# ZHSD-USB-UART.net
KiCad netlist of a schematic drawn in Altium Designer
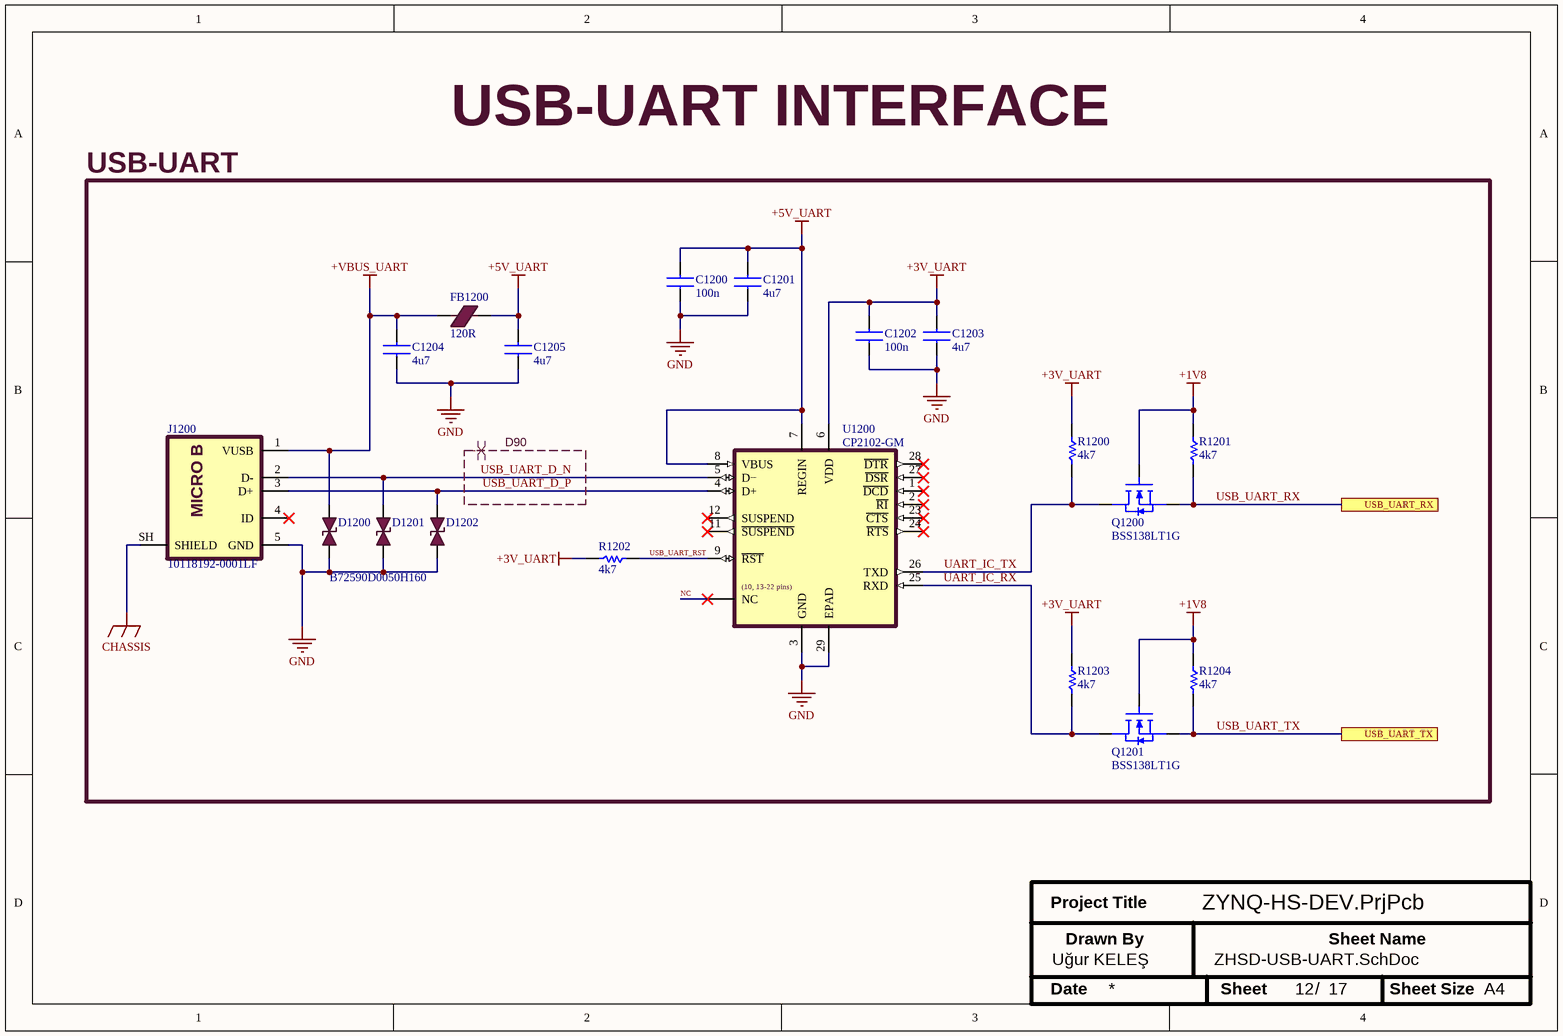
[diagram p0: ZHSD-USB-UART.SchDoc]

(export (version "E")
  (design (tool "Eeschema 10.0.6"))
  (components
    (comp (ref "C1200")
      (value "100n")
      (footprint "0603CAPC1608X09N")
      (description "CAP CER 0.1UF 16V X7R 0402 (1005) ±10%")
      (fields (field (name "MANUFACTURER") "Murata Electronics") (field (name "MPN") "GRM155R71C104KA88J"))
      (libsource (lib "UK_Library") (part "GRM155R71C104KA88J"))
    )
    (comp (ref "C1201")
      (value "4u7")
      (footprint "0603CAPC1608X09N")
      (description "CAP CER 4.7UF 10V X5R 0603 (1608) ±10%")
      (fields
        (field (name "MANUFACTURER") "Samsung Electro-Mechanics")
        (field (name "MPN") "CL10A475KP8NNNC")
      )
      (libsource (lib "UK_Library") (part "CL10A475KP8NNNC"))
    )
    (comp (ref "C1202")
      (value "100n")
      (footprint "0603CAPC1608X09N")
      (description "CAP CER 0.1UF 16V X7R 0402 (1005) ±10%")
      (fields (field (name "MANUFACTURER") "Murata Electronics") (field (name "MPN") "GRM155R71C104KA88J"))
      (libsource (lib "UK_Library") (part "GRM155R71C104KA88J"))
    )
    (comp (ref "C1203")
      (value "4u7")
      (footprint "0603CAPC1608X09N")
      (description "CAP CER 4.7UF 10V X5R 0603 (1608) ±10%")
      (fields
        (field (name "MANUFACTURER") "Samsung Electro-Mechanics")
        (field (name "MPN") "CL10A475KP8NNNC")
      )
      (libsource (lib "UK_Library") (part "CL10A475KP8NNNC"))
    )
    (comp (ref "C1204")
      (value "4u7")
      (footprint "0603CAPC1608X09N")
      (description "CAP CER 4.7UF 10V X5R 0603 (1608) ±10%")
      (fields
        (field (name "MANUFACTURER") "Samsung Electro-Mechanics")
        (field (name "MPN") "CL10A475KP8NNNC")
      )
      (libsource (lib "UK_Library") (part "CL10A475KP8NNNC"))
    )
    (comp (ref "C1205")
      (value "4u7")
      (footprint "0603CAPC1608X09N")
      (description "CAP CER 4.7UF 10V X5R 0603 (1608) ±10%")
      (fields
        (field (name "MANUFACTURER") "Samsung Electro-Mechanics")
        (field (name "MPN") "CL10A475KP8NNNC")
      )
      (libsource (lib "UK_Library") (part "CL10A475KP8NNNC"))
    )
    (comp (ref "D1200")
      (value "B72590D0050H160")
      (footprint "0402DIOC1005X06N")
      (description "Varistor 1 Circuit Surface Mount, MLCV 0402 (1005 Metric)")
      (fields (field (name "MANUFACTURER") "EPCOS - TDK Electronics"))
      (libsource (lib "UK_Library") (part "B72590D0050H160"))
    )
    (comp (ref "D1201")
      (value "B72590D0050H160")
      (footprint "0402DIOC1005X06N")
      (description "Varistor 1 Circuit Surface Mount, MLCV 0402 (1005 Metric)")
      (fields (field (name "MANUFACTURER") "EPCOS - TDK Electronics"))
      (libsource (lib "UK_Library") (part "B72590D0050H160"))
    )
    (comp (ref "D1202")
      (value "B72590D0050H160")
      (footprint "0402DIOC1005X06N")
      (description "Varistor 1 Circuit Surface Mount, MLCV 0402 (1005 Metric)")
      (fields (field (name "MANUFACTURER") "EPCOS - TDK Electronics"))
      (libsource (lib "UK_Library") (part "B72590D0050H160"))
    )
    (comp (ref "FB1200")
      (value "120R")
      (footprint "0603INDC1608X08N")
      (description "FERRITE BEAD 120 OHM 0603 (1608) 3A 25mOhm")
      (fields (field (name "MANUFACTURER") "Murata Electronics") (field (name "MPN") "BLM18SG121TN1D"))
      (libsource (lib "UK_Library") (part "BLM18SG121TN1D"))
    )
    (comp (ref "J1200")
      (value "10118192-0001LF")
      (footprint "USB2.0 MICRO B SMD")
      (description "CONN RCPT USB2.0 MICRO B SMD R/A")
      (fields (field (name "MANUFACTURER") "Amphenol ICC (FCI)"))
      (libsource (lib "UK_Library") (part "USB-MICRO-B"))
    )
    (comp (ref "Q1200")
      (value "BSS138LT1G")
      (footprint "SOT95P237X89-3N")
      (description "N-Channel 50 V 200mA (Ta) 225mW (Ta) Surface Mount SOT-23-3 (TO-236)")
      (fields (field (name "MANUFACTURER") "onsemi"))
      (libsource (lib "UK_Library") (part "BSS138LT1G"))
    )
    (comp (ref "Q1201")
      (value "BSS138LT1G")
      (footprint "SOT95P237X89-3N")
      (description "N-Channel 50 V 200mA (Ta) 225mW (Ta) Surface Mount SOT-23-3 (TO-236)")
      (fields (field (name "MANUFACTURER") "onsemi"))
      (libsource (lib "UK_Library") (part "BSS138LT1G"))
    )
    (comp (ref "R1200")
      (value "4k7")
      (footprint "0402RESC1005X04N")
      (description "RES 4.7K OHM 5% 1/16W 0402 (1005)")
      (fields (field (name "MANUFACTURER") "YAGEO") (field (name "MPN") "RT0402FRE0780RL"))
      (libsource (lib "UK_Library") (part "RC0402JR-074K7L"))
    )
    (comp (ref "R1201")
      (value "4k7")
      (footprint "0402RESC1005X04N")
      (description "RES 4.7K OHM 5% 1/16W 0402 (1005)")
      (fields (field (name "MANUFACTURER") "YAGEO") (field (name "MPN") "RT0402FRE0780RL"))
      (libsource (lib "UK_Library") (part "RC0402JR-074K7L"))
    )
    (comp (ref "R1202")
      (value "4k7")
      (footprint "0402RESC1005X04N")
      (description "RES 4.7K OHM 5% 1/16W 0402 (1005)")
      (fields (field (name "MANUFACTURER") "YAGEO") (field (name "MPN") "RT0402FRE0780RL"))
      (libsource (lib "UK_Library") (part "RC0402JR-074K7L"))
    )
    (comp (ref "R1203")
      (value "4k7")
      (footprint "0402RESC1005X04N")
      (description "RES 4.7K OHM 5% 1/16W 0402 (1005)")
      (fields (field (name "MANUFACTURER") "YAGEO") (field (name "MPN") "RT0402FRE0780RL"))
      (libsource (lib "UK_Library") (part "RC0402JR-074K7L"))
    )
    (comp (ref "R1204")
      (value "4k7")
      (footprint "0402RESC1005X04N")
      (description "RES 4.7K OHM 5% 1/16W 0402 (1005)")
      (fields (field (name "MANUFACTURER") "YAGEO") (field (name "MPN") "RT0402FRE0780RL"))
      (libsource (lib "UK_Library") (part "RC0402JR-074K7L"))
    )
    (comp (ref "U1200")
      (value "CP2102-GM")
      (footprint "QFN50P500X500X100_HS-29N")
      (description "USB Bridge, USB to UART USB 2.0 UART Interface 28-QFN (5x5)")
      (fields (field (name "MANUFACTURER") "Silicon Labs"))
      (libsource (lib "UK_Library") (part "CP2102-GM"))
    )
  )
  (nets
    (net (code "1") (name "+1V8") (class "Default")
      (node (ref "Q1200") (pin "1") (pinfunction "G_1") (pintype "passive"))
      (node (ref "Q1201") (pin "1") (pinfunction "G_1") (pintype "passive"))
      (node (ref "R1201") (pin "1") (pinfunction "1_1") (pintype "passive"))
      (node (ref "R1204") (pin "1") (pinfunction "1_1") (pintype "passive"))
    )
    (net (code "2") (name "+3V_UART") (class "Default")
      (node (ref "C1202") (pin "2") (pinfunction "2_2") (pintype "passive"))
      (node (ref "C1203") (pin "2") (pinfunction "2_2") (pintype "passive"))
      (node (ref "R1200") (pin "1") (pinfunction "1_1") (pintype "passive"))
      (node (ref "R1202") (pin "2") (pinfunction "2_2") (pintype "passive"))
      (node (ref "R1203") (pin "1") (pinfunction "1_1") (pintype "passive"))
      (node (ref "U1200") (pin "6") (pinfunction "VDD_6") (pintype "power_in"))
    )
    (net (code "3") (name "+5V_UART") (class "Default")
      (node (ref "C1200") (pin "2") (pinfunction "2_2") (pintype "passive"))
      (node (ref "C1201") (pin "2") (pinfunction "2_2") (pintype "passive"))
      (node (ref "C1205") (pin "2") (pinfunction "2_2") (pintype "passive"))
      (node (ref "FB1200") (pin "2") (pinfunction "2_2") (pintype "passive"))
      (node (ref "U1200") (pin "7") (pinfunction "REGIN_7") (pintype "power_in"))
      (node (ref "U1200") (pin "8") (pinfunction "VBUS_8") (pintype "input"))
    )
    (net (code "4") (name "+VBUS_UART") (class "Default")
      (node (ref "C1204") (pin "2") (pinfunction "2_2") (pintype "passive"))
      (node (ref "D1200") (pin "2") (pinfunction "2_2") (pintype "passive"))
      (node (ref "FB1200") (pin "1") (pinfunction "1_1") (pintype "passive"))
      (node (ref "J1200") (pin "1") (pinfunction "VUSB_1") (pintype "passive"))
    )
    (net (code "5") (name "/NC") (class "Default")
      (node (ref "U1200") (pin "NC") (pinfunction "NC_NC") (pintype "passive+no_connect"))
    )
    (net (code "6") (name "/UART_IC_RX") (class "Default")
      (node (ref "Q1201") (pin "3") (pinfunction "D_3") (pintype "passive"))
      (node (ref "R1203") (pin "2") (pinfunction "2_2") (pintype "passive"))
      (node (ref "U1200") (pin "25") (pinfunction "RXD_25") (pintype "input"))
    )
    (net (code "7") (name "/UART_IC_TX") (class "Default")
      (node (ref "Q1200") (pin "3") (pinfunction "D_3") (pintype "passive"))
      (node (ref "R1200") (pin "2") (pinfunction "2_2") (pintype "passive"))
      (node (ref "U1200") (pin "26") (pinfunction "TXD_26") (pintype "output"))
    )
    (net (code "8") (name "/USB_UART_D_N") (class "Default")
      (node (ref "D1201") (pin "2") (pinfunction "2_2") (pintype "passive"))
      (node (ref "J1200") (pin "2") (pinfunction "D-_2") (pintype "passive"))
      (node (ref "U1200") (pin "5") (pinfunction "D−_5") (pintype "bidirectional"))
    )
    (net (code "9") (name "/USB_UART_D_P") (class "Default")
      (node (ref "D1202") (pin "2") (pinfunction "2_2") (pintype "passive"))
      (node (ref "J1200") (pin "3") (pinfunction "D+_3") (pintype "passive"))
      (node (ref "U1200") (pin "4") (pinfunction "D+_4") (pintype "bidirectional"))
    )
    (net (code "10") (name "/USB_UART_RST") (class "Default")
      (node (ref "R1202") (pin "1") (pinfunction "1_1") (pintype "passive"))
      (node (ref "U1200") (pin "9") (pinfunction "RST_9") (pintype "bidirectional"))
    )
    (net (code "11") (name "/USB_UART_RX") (class "Default")
      (node (ref "Q1200") (pin "2") (pinfunction "S_2") (pintype "passive"))
      (node (ref "R1201") (pin "2") (pinfunction "2_2") (pintype "passive"))
    )
    (net (code "12") (name "/USB_UART_TX") (class "Default")
      (node (ref "Q1201") (pin "2") (pinfunction "S_2") (pintype "passive"))
      (node (ref "R1204") (pin "2") (pinfunction "2_2") (pintype "passive"))
    )
    (net (code "13") (name "CHASSIS") (class "Default")
      (node (ref "J1200") (pin "SH") (pinfunction "SHIELD_SH") (pintype "passive"))
    )
    (net (code "14") (name "GND") (class "Default")
      (node (ref "C1200") (pin "1") (pinfunction "1_1") (pintype "passive"))
      (node (ref "C1201") (pin "1") (pinfunction "1_1") (pintype "passive"))
      (node (ref "C1202") (pin "1") (pinfunction "1_1") (pintype "passive"))
      (node (ref "C1203") (pin "1") (pinfunction "1_1") (pintype "passive"))
      (node (ref "C1204") (pin "1") (pinfunction "1_1") (pintype "passive"))
      (node (ref "C1205") (pin "1") (pinfunction "1_1") (pintype "passive"))
      (node (ref "D1200") (pin "1") (pinfunction "1_1") (pintype "passive"))
      (node (ref "D1201") (pin "1") (pinfunction "1_1") (pintype "passive"))
      (node (ref "D1202") (pin "1") (pinfunction "1_1") (pintype "passive"))
      (node (ref "J1200") (pin "5") (pinfunction "GND_5") (pintype "passive"))
      (node (ref "U1200") (pin "29") (pinfunction "EPAD_29") (pintype "power_in"))
      (node (ref "U1200") (pin "3") (pinfunction "GND_3") (pintype "power_in"))
    )
    (net (code "15") (name "unconnected-(J1200-ID-Pad4)") (class "Default")
      (node (ref "J1200") (pin "4") (pinfunction "ID_4") (pintype "passive+no_connect"))
    )
    (net (code "16") (name "unconnected-(U1200-CTS-Pad23)") (class "Default")
      (node (ref "U1200") (pin "23") (pinfunction "CTS_23") (pintype "input+no_connect"))
    )
    (net (code "17") (name "unconnected-(U1200-DCD-Pad1)") (class "Default")
      (node (ref "U1200") (pin "1") (pinfunction "DCD_1") (pintype "input+no_connect"))
    )
    (net (code "18") (name "unconnected-(U1200-DSR-Pad27)") (class "Default")
      (node (ref "U1200") (pin "27") (pinfunction "DSR_27") (pintype "input+no_connect"))
    )
    (net (code "19") (name "unconnected-(U1200-DTR-Pad28)") (class "Default")
      (node (ref "U1200") (pin "28") (pinfunction "DTR_28") (pintype "output+no_connect"))
    )
    (net (code "20") (name "unconnected-(U1200-RI-Pad2)") (class "Default")
      (node (ref "U1200") (pin "2") (pinfunction "RI_2") (pintype "input+no_connect"))
    )
    (net (code "21") (name "unconnected-(U1200-RTS-Pad24)") (class "Default")
      (node (ref "U1200") (pin "24") (pinfunction "RTS_24") (pintype "output+no_connect"))
    )
    (net (code "22") (name "unconnected-(U1200-SUSPEND-Pad11)") (class "Default")
      (node (ref "U1200") (pin "11") (pinfunction "SUSPEND_11") (pintype "output+no_connect"))
    )
    (net (code "23") (name "unconnected-(U1200-SUSPEND-Pad12)") (class "Default")
      (node (ref "U1200") (pin "12") (pinfunction "SUSPEND_12") (pintype "output+no_connect"))
    )
  )
)
